# GATE_BOARD.net
KiCad netlist of a schematic drawn in Altium Designer
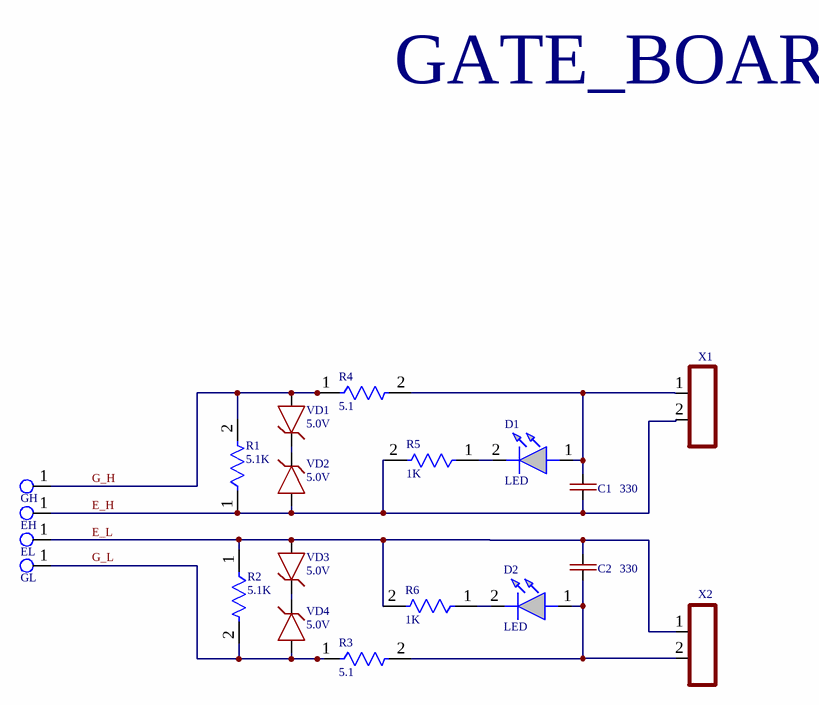
[diagram p0: GATE_BOARD.SchDoc]

(export (version "E")
  (design (tool "Eeschema 10.0.6"))
  (components
    (comp (ref "C1")
      (value "330")
      (footprint "CAP-0805")
      (libsource (lib "PASSIVE_COMPONENTS") (part "CAP-NON-POLAR"))
    )
    (comp (ref "C2")
      (value "330")
      (footprint "CAP-0805")
      (libsource (lib "PASSIVE_COMPONENTS") (part "CAP-NON-POLAR"))
    )
    (comp (ref "D1")
      (value "LED")
      (footprint "LED_BLUE")
      (description "WURTH ELEKTRONIK - 151031YS06000 - LED, Yellow, Through Hole, T-1 (3mm), 30 mA, 2 V, 590 nm")
      (fields
        (field (name "MANUFACTURER_PART_NUMBER") "151031YS06000")
        (field (name "MOUSER PART NUMBER") "710-151031YS06000")
      )
      (libsource (lib "Optic-LED") (part "LED"))
    )
    (comp (ref "D2")
      (value "LED")
      (footprint "LED_BLUE")
      (description "WURTH ELEKTRONIK - 151031YS06000 - LED, Yellow, Through Hole, T-1 (3mm), 30 mA, 2 V, 590 nm")
      (fields
        (field (name "MANUFACTURER_PART_NUMBER") "151031YS06000")
        (field (name "MOUSER PART NUMBER") "710-151031YS06000")
      )
      (libsource (lib "Optic-LED") (part "LED"))
    )
    (comp (ref "EH")
      (value "~")
      (footprint "Test_Point")
      (description "Test_Point")
      (libsource (lib "Connectors") (part "TP_PCB?"))
    )
    (comp (ref "EL")
      (value "~")
      (footprint "Test_Point")
      (description "Test_Point")
      (libsource (lib "Connectors") (part "TP_PCB?"))
    )
    (comp (ref "GH")
      (value "~")
      (footprint "Test_Point")
      (description "Test_Point")
      (libsource (lib "Connectors") (part "TP_PCB?"))
    )
    (comp (ref "GL")
      (value "~")
      (footprint "Test_Point")
      (description "Test_Point")
      (libsource (lib "Connectors") (part "TP_PCB?"))
    )
    (comp (ref "R1")
      (value "5.1K")
      (footprint "RES-1206")
      (libsource (lib "PASSIVE_COMPONENTS") (part "RES-CONST"))
    )
    (comp (ref "R2")
      (value "5.1K")
      (footprint "RES-1206")
      (libsource (lib "PASSIVE_COMPONENTS") (part "RES-CONST"))
    )
    (comp (ref "R3")
      (value "5.1")
      (footprint "RES-1206")
      (libsource (lib "PASSIVE_COMPONENTS") (part "RES-CONST"))
    )
    (comp (ref "R4")
      (value "5.1")
      (footprint "RES-1206")
      (libsource (lib "PASSIVE_COMPONENTS") (part "RES-CONST"))
    )
    (comp (ref "R5")
      (value "1K")
      (footprint "RES-0805")
      (libsource (lib "PASSIVE_COMPONENTS") (part "RES-CONST"))
    )
    (comp (ref "R6")
      (value "1K")
      (footprint "RES-0805")
      (libsource (lib "PASSIVE_COMPONENTS") (part "RES-CONST"))
    )
    (comp (ref "VD1") (value "5.0V") (footprint "DO-214AA") (libsource (lib "Diodes") (part "SMBJ15A")))
    (comp (ref "VD2") (value "5.0V") (footprint "DO-214AA") (libsource (lib "Diodes") (part "SMBJ15A")))
    (comp (ref "VD3") (value "5.0V") (footprint "DO-214AA") (libsource (lib "Diodes") (part "SMBJ15A")))
    (comp (ref "VD4") (value "5.0V") (footprint "DO-214AA") (libsource (lib "Diodes") (part "SMBJ15A")))
    (comp (ref "X1")
      (value "CONN-2-PIN")
      (footprint "CONN-PLS-2-2.54mm")
      (libsource (lib "XH 2PIN") (part "CONN-2-PIN"))
    )
    (comp (ref "X2")
      (value "CONN-2-PIN")
      (footprint "CONN-PLS-2-2.54mm")
      (libsource (lib "XH 2PIN") (part "CONN-2-PIN"))
    )
  )
  (nets
    (net (code "1") (name "/E_H") (class "Default")
      (node (ref "C1") (pin "1") (pinfunction "1_1") (pintype "passive"))
      (node (ref "EH") (pin "1") (pinfunction "G9_1") (pintype "passive"))
      (node (ref "R1") (pin "1") (pinfunction "1_1") (pintype "passive"))
      (node (ref "R5") (pin "2") (pinfunction "2_2") (pintype "passive"))
      (node (ref "VD2") (pin "1") (pinfunction "A_1") (pintype "passive"))
      (node (ref "X1") (pin "2") (pinfunction "2_2") (pintype "passive"))
    )
    (net (code "5") (name "/E_L") (class "Default")
      (node (ref "C2") (pin "2") (pinfunction "2_2") (pintype "passive"))
      (node (ref "EL") (pin "1") (pinfunction "G9_1") (pintype "passive"))
      (node (ref "R2") (pin "1") (pinfunction "1_1") (pintype "passive"))
      (node (ref "R6") (pin "2") (pinfunction "2_2") (pintype "passive"))
      (node (ref "VD3") (pin "1") (pinfunction "A_1") (pintype "passive"))
      (node (ref "X2") (pin "1") (pinfunction "1_1") (pintype "passive"))
    )
    (net (code "6") (name "/G_H") (class "Default")
      (node (ref "GH") (pin "1") (pinfunction "G9_1") (pintype "passive"))
      (node (ref "R1") (pin "2") (pinfunction "2_2") (pintype "passive"))
      (node (ref "R4") (pin "1") (pinfunction "1_1") (pintype "passive"))
      (node (ref "VD1") (pin "1") (pinfunction "A_1") (pintype "passive"))
    )
    (net (code "7") (name "/G_L") (class "Default")
      (node (ref "GL") (pin "1") (pinfunction "G9_1") (pintype "passive"))
      (node (ref "R2") (pin "2") (pinfunction "2_2") (pintype "passive"))
      (node (ref "R3") (pin "1") (pinfunction "1_1") (pintype "passive"))
      (node (ref "VD4") (pin "1") (pinfunction "A_1") (pintype "passive"))
    )
    (net (code "8") (name "Net-(D1-A)") (class "Default")
      (node (ref "C1") (pin "2") (pinfunction "2_2") (pintype "passive"))
      (node (ref "D1") (pin "1") (pinfunction "A_1") (pintype "passive"))
      (node (ref "R4") (pin "2") (pinfunction "2_2") (pintype "passive"))
      (node (ref "X1") (pin "1") (pinfunction "1_1") (pintype "passive"))
    )
    (net (code "9") (name "Net-(D1-K)") (class "Default")
      (node (ref "D1") (pin "2") (pinfunction "K_2") (pintype "passive"))
      (node (ref "R5") (pin "1") (pinfunction "1_1") (pintype "passive"))
    )
    (net (code "10") (name "Net-(D2-A)") (class "Default")
      (node (ref "C2") (pin "1") (pinfunction "1_1") (pintype "passive"))
      (node (ref "D2") (pin "1") (pinfunction "A_1") (pintype "passive"))
      (node (ref "R3") (pin "2") (pinfunction "2_2") (pintype "passive"))
      (node (ref "X2") (pin "2") (pinfunction "2_2") (pintype "passive"))
    )
    (net (code "11") (name "Net-(D2-K)") (class "Default")
      (node (ref "D2") (pin "2") (pinfunction "K_2") (pintype "passive"))
      (node (ref "R6") (pin "1") (pinfunction "1_1") (pintype "passive"))
    )
    (net (code "12") (name "Net-(VD1-C)") (class "Default")
      (node (ref "VD1") (pin "2") (pinfunction "C_2") (pintype "passive"))
      (node (ref "VD2") (pin "2") (pinfunction "C_2") (pintype "passive"))
    )
    (net (code "13") (name "Net-(VD3-C)") (class "Default")
      (node (ref "VD3") (pin "2") (pinfunction "C_2") (pintype "passive"))
      (node (ref "VD4") (pin "2") (pinfunction "C_2") (pintype "passive"))
    )
  )
)
